# Top_Level.net
KiCad netlist of a schematic drawn in Altium Designer
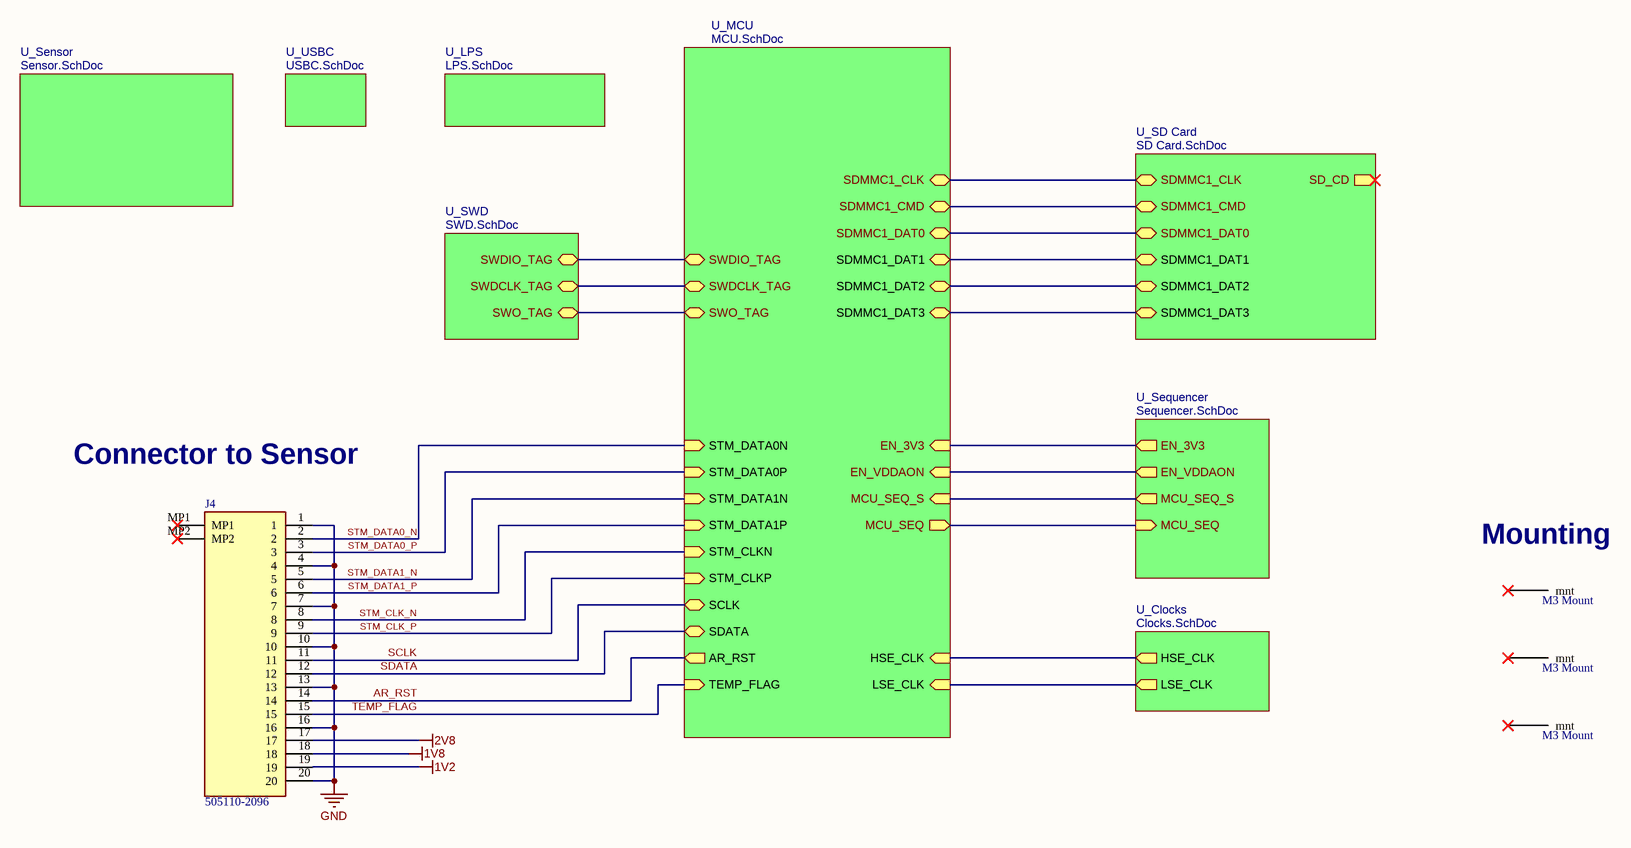
[diagram p0: Top Level.SchDoc]

(export (version "E")
  (design (tool "Eeschema 10.0.6"))
  (components
    (comp (ref "J4")
      (value "505110-2096")
      (footprint "5051102096")
      (description "Connector")
      (fields (field (name "MOUSER PART NUMBER") "538-505110-2096"))
      (libsource (lib "C2S") (part "505110-2096"))
    )
    (comp (ref "MNT1")
      (value "M3 Mount")
      (footprint "M3_Mount-Footprint-1")
      (description "M3 mounting hole")
      (fields (field (name "AUTHOR") "Raphael Ho"))
      (libsource (lib "Perth Aerospace Student Team") (part "M3_Mount-Symbol-1"))
    )
    (comp (ref "MNT2")
      (value "M3 Mount")
      (footprint "M3_Mount-Footprint-1")
      (description "M3 mounting hole")
      (fields (field (name "AUTHOR") "Raphael Ho"))
      (libsource (lib "Perth Aerospace Student Team") (part "M3_Mount-Symbol-1"))
    )
    (comp (ref "MNT3")
      (value "M3 Mount")
      (footprint "M3_Mount-Footprint-1")
      (description "M3 mounting hole")
      (fields (field (name "AUTHOR") "Raphael Ho"))
      (libsource (lib "Perth Aerospace Student Team") (part "M3_Mount-Symbol-1"))
    )
  )
  (nets
    (net (code "1") (name "/AR_RST") (class "Default")
      (node (ref "J4") (pin "14") (pinfunction "14_14") (pintype "passive"))
    )
    (net (code "8") (name "/SCLK") (class "Default")
      (node (ref "J4") (pin "11") (pinfunction "11_11") (pintype "passive"))
    )
    (net (code "9") (name "/SDATA") (class "Default")
      (node (ref "J4") (pin "12") (pinfunction "12_12") (pintype "passive"))
    )
    (net (code "17") (name "/STM_CLK_N") (class "Default")
      (node (ref "J4") (pin "8") (pinfunction "8_8") (pintype "passive"))
    )
    (net (code "18") (name "/STM_CLK_P") (class "Default")
      (node (ref "J4") (pin "9") (pinfunction "9_9") (pintype "passive"))
    )
    (net (code "19") (name "/STM_DATA0_N") (class "Default")
      (node (ref "J4") (pin "2") (pinfunction "2_2") (pintype "passive"))
    )
    (net (code "20") (name "/STM_DATA0_P") (class "Default")
      (node (ref "J4") (pin "3") (pinfunction "3_3") (pintype "passive"))
    )
    (net (code "21") (name "/STM_DATA1_N") (class "Default")
      (node (ref "J4") (pin "5") (pinfunction "5_5") (pintype "passive"))
    )
    (net (code "22") (name "/STM_DATA1_P") (class "Default")
      (node (ref "J4") (pin "6") (pinfunction "6_6") (pintype "passive"))
    )
    (net (code "26") (name "/TEMP_FLAG") (class "Default")
      (node (ref "J4") (pin "15") (pinfunction "15_15") (pintype "passive"))
    )
    (net (code "27") (name "1V2") (class "Default")
      (node (ref "J4") (pin "19") (pinfunction "19_19") (pintype "passive"))
    )
    (net (code "28") (name "1V8") (class "Default")
      (node (ref "J4") (pin "18") (pinfunction "18_18") (pintype "passive"))
    )
    (net (code "29") (name "2V8") (class "Default")
      (node (ref "J4") (pin "17") (pinfunction "17_17") (pintype "passive"))
    )
    (net (code "30") (name "GND") (class "Default")
      (node (ref "J4") (pin "1") (pinfunction "1_1") (pintype "passive"))
      (node (ref "J4") (pin "10") (pinfunction "10_10") (pintype "passive"))
      (node (ref "J4") (pin "13") (pinfunction "13_13") (pintype "passive"))
      (node (ref "J4") (pin "16") (pinfunction "16_16") (pintype "passive"))
      (node (ref "J4") (pin "20") (pinfunction "20_20") (pintype "passive"))
      (node (ref "J4") (pin "4") (pinfunction "4_4") (pintype "passive"))
      (node (ref "J4") (pin "7") (pinfunction "7_7") (pintype "passive"))
    )
    (net (code "31") (name "unconnected-(J4-PadMP1)") (class "Default")
      (node (ref "J4") (pin "MP1") (pinfunction "MP1_MP1") (pintype "passive+no_connect"))
    )
    (net (code "32") (name "unconnected-(J4-PadMP2)") (class "Default")
      (node (ref "J4") (pin "MP2") (pinfunction "MP2_MP2") (pintype "passive+no_connect"))
    )
    (net (code "33") (name "unconnected-(MNT1-mnt-Pad1)") (class "Default")
      (node (ref "MNT1") (pin "1") (pinfunction "mnt_1") (pintype "passive+no_connect"))
    )
    (net (code "34") (name "unconnected-(MNT2-mnt-Pad1)") (class "Default")
      (node (ref "MNT2") (pin "1") (pinfunction "mnt_1") (pintype "passive+no_connect"))
    )
    (net (code "35") (name "unconnected-(MNT3-mnt-Pad1)") (class "Default")
      (node (ref "MNT3") (pin "1") (pinfunction "mnt_1") (pintype "passive+no_connect"))
    )
  )
)
